# kooz_v0_1.net
KiCad netlist of a schematic drawn in EAGLE
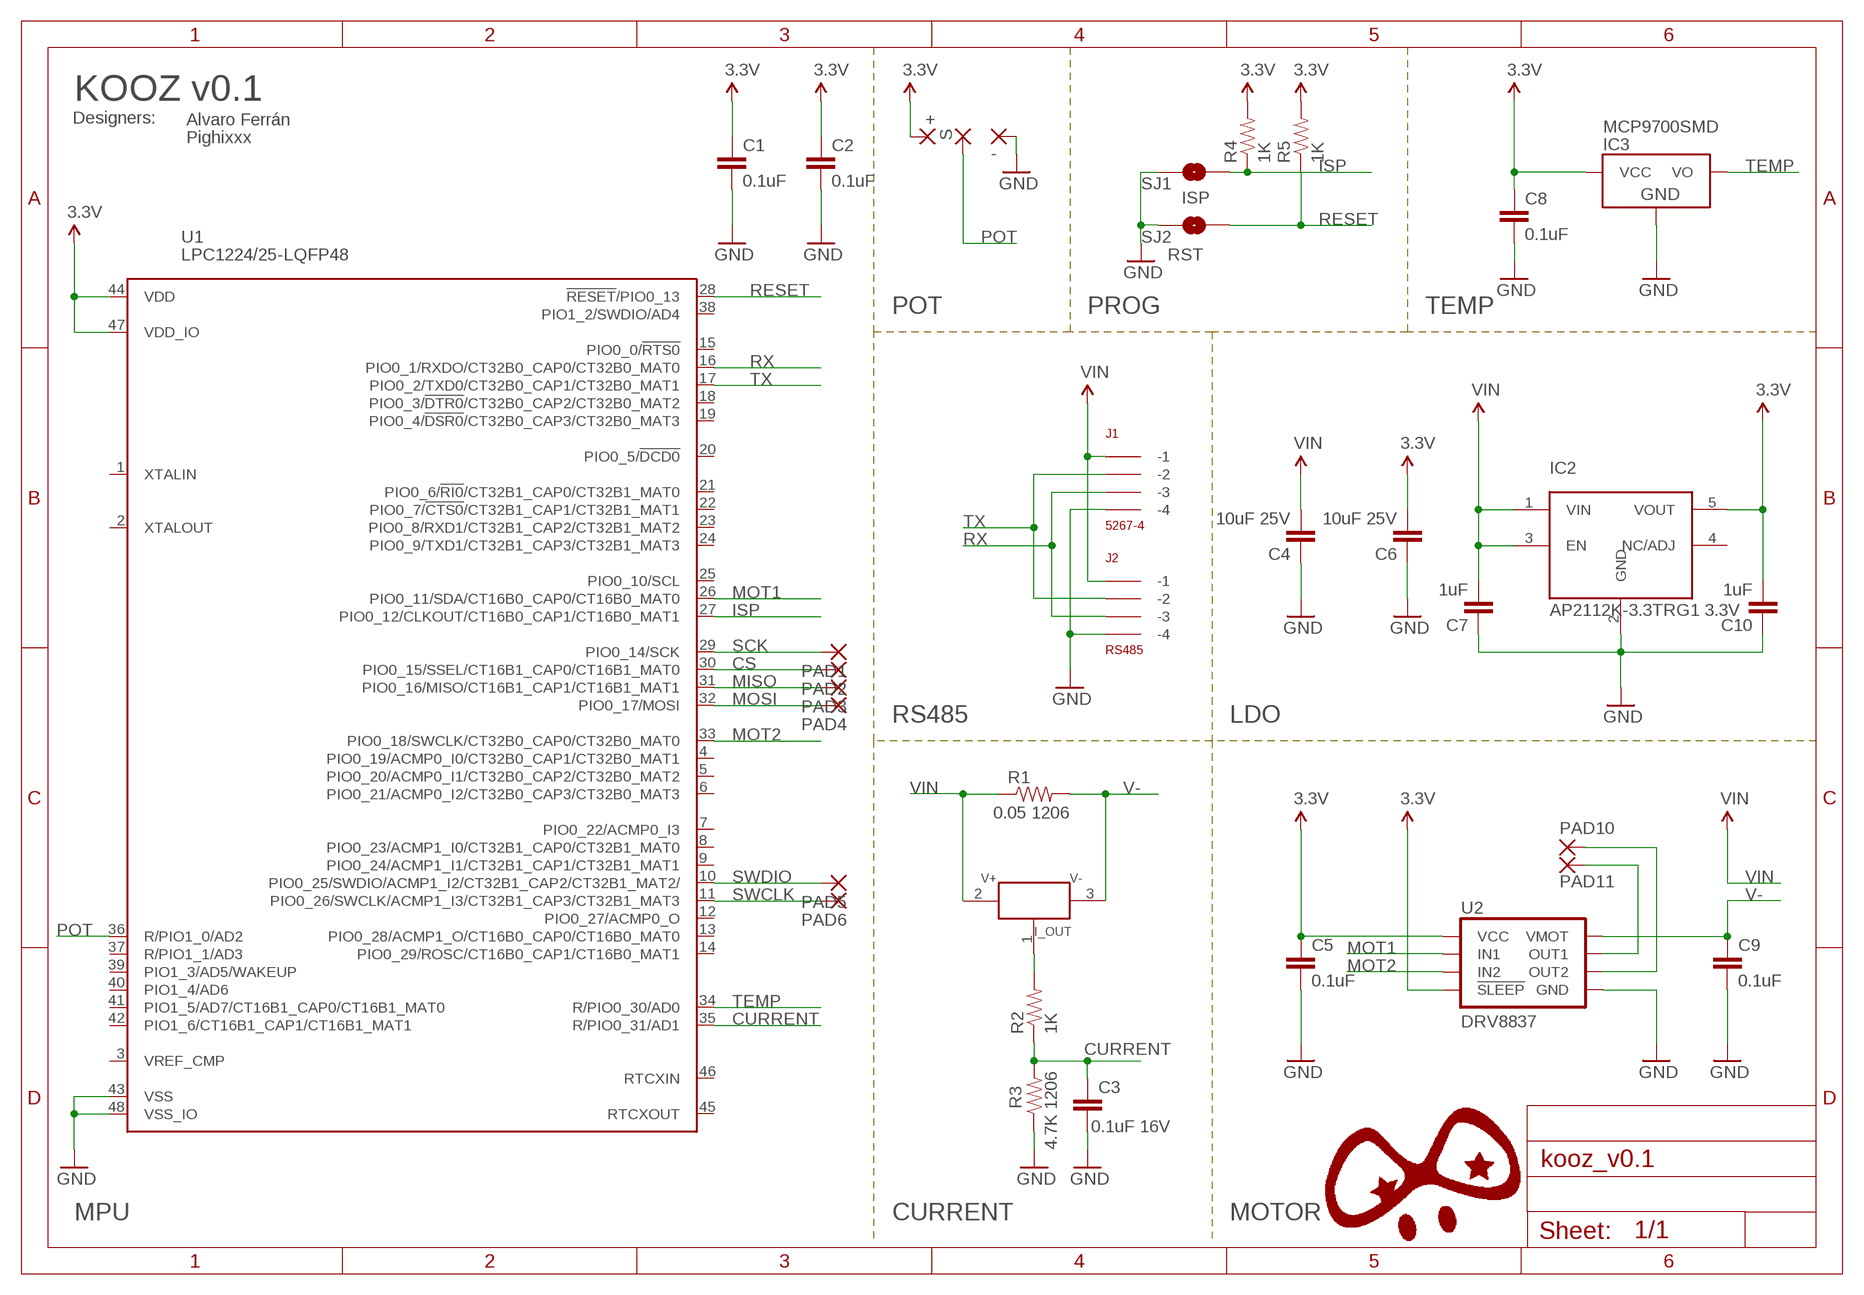
[diagram p0: schematic, sheet 1]

(export (version "E")
  (design (tool "Eeschema 10.0.6"))
  (components
    (comp (ref "C1")
      (value "0.1uF")
      (footprint "eagle-import:0402-CAP")
      (libsource (lib "eagle-import") (part "CAP0402-CAP"))
    )
    (comp (ref "C2")
      (value "0.1uF")
      (footprint "eagle-import:0402-CAP")
      (libsource (lib "eagle-import") (part "CAP0402-CAP"))
    )
    (comp (ref "C3")
      (value "0.1uF 16V")
      (footprint "eagle-import:0402-CAP")
      (libsource (lib "eagle-import") (part "CAP0402-CAP"))
    )
    (comp (ref "C4")
      (value "10uF 25V")
      (footprint "eagle-import:0603-CAP")
      (libsource (lib "eagle-import") (part "CAP0603-CAP"))
    )
    (comp (ref "C5")
      (value "0.1uF")
      (footprint "eagle-import:0402-CAP")
      (libsource (lib "eagle-import") (part "CAP0402-CAP"))
    )
    (comp (ref "C6")
      (value "10uF 25V")
      (footprint "eagle-import:0603-CAP")
      (libsource (lib "eagle-import") (part "CAP0603-CAP"))
    )
    (comp (ref "C7")
      (value "1uF")
      (footprint "eagle-import:0402-CAP")
      (libsource (lib "eagle-import") (part "CAP0402-CAP"))
    )
    (comp (ref "C8")
      (value "0.1uF")
      (footprint "eagle-import:0402-CAP")
      (libsource (lib "eagle-import") (part "CAP0402-CAP"))
    )
    (comp (ref "C9")
      (value "0.1uF")
      (footprint "eagle-import:0402-CAP")
      (libsource (lib "eagle-import") (part "CAP0402-CAP"))
    )
    (comp (ref "C10")
      (value "1uF")
      (footprint "eagle-import:0402-CAP")
      (libsource (lib "eagle-import") (part "CAP0402-CAP"))
    )
    (comp (ref "IC1")
      (value "ZXCT1008")
      (footprint "eagle-import:SOT23")
      (libsource (lib "eagle-import") (part "ZXCT1008"))
    )
    (comp (ref "IC2")
      (value "AP2112K-3.3TRG1 3.3V")
      (footprint "eagle-import:SOT23-5")
      (libsource (lib "eagle-import") (part "5PIN_REG"))
    )
    (comp (ref "IC3")
      (value "MCP9700SMD")
      (footprint "eagle-import:SOT23-3")
      (libsource (lib "eagle-import") (part "MCP9700SMD"))
    )
    (comp (ref "J1")
      (value "5267-4")
      (footprint "eagle-import:5267-4")
      (libsource (lib "eagle-import") (part "5267-4"))
    )
    (comp (ref "J2")
      (value "RS485")
      (footprint "eagle-import:5267-4")
      (libsource (lib "eagle-import") (part "5267-4"))
    )
    (comp (ref "PAD1")
      (value "SMD2")
      (footprint "eagle-import:SMD1,27-2,54")
      (libsource (lib "eagle-import") (part "SMD2"))
    )
    (comp (ref "PAD2")
      (value "SMD2")
      (footprint "eagle-import:SMD1,27-2,54")
      (libsource (lib "eagle-import") (part "SMD2"))
    )
    (comp (ref "PAD3")
      (value "SMD2")
      (footprint "eagle-import:SMD1,27-2,54")
      (libsource (lib "eagle-import") (part "SMD2"))
    )
    (comp (ref "PAD4")
      (value "SMD2")
      (footprint "eagle-import:SMD1,27-2,54")
      (libsource (lib "eagle-import") (part "SMD2"))
    )
    (comp (ref "PAD5")
      (value "SMD2")
      (footprint "eagle-import:SMD1,27-2,54")
      (libsource (lib "eagle-import") (part "SMD2"))
    )
    (comp (ref "PAD6")
      (value "SMD2")
      (footprint "eagle-import:SMD1,27-2,54")
      (libsource (lib "eagle-import") (part "SMD2"))
    )
    (comp (ref "PAD7")
      (value "+")
      (footprint "eagle-import:2,54_1,1")
      (libsource (lib "eagle-import") (part "2,54/1,1"))
    )
    (comp (ref "PAD8")
      (value "S")
      (footprint "eagle-import:2,54_1,1")
      (libsource (lib "eagle-import") (part "2,54/1,1"))
    )
    (comp (ref "PAD9")
      (value "-")
      (footprint "eagle-import:2,54_1,1")
      (libsource (lib "eagle-import") (part "2,54/1,1"))
    )
    (comp (ref "PAD10")
      (value "2,54/1,1")
      (footprint "eagle-import:2,54_1,1")
      (libsource (lib "eagle-import") (part "2,54/1,1"))
    )
    (comp (ref "PAD11")
      (value "2,54/1,1")
      (footprint "eagle-import:2,54_1,1")
      (libsource (lib "eagle-import") (part "2,54/1,1"))
    )
    (comp (ref "R1")
      (value "0.05 1206")
      (footprint "eagle-import:1206-RES")
      (libsource (lib "eagle-import") (part "RESISTOR"))
    )
    (comp (ref "R2")
      (value "1K")
      (footprint "eagle-import:0402-RES")
      (libsource (lib "eagle-import") (part "RESISTOR0402-RES"))
    )
    (comp (ref "R3")
      (value "4.7K 1206")
      (footprint "eagle-import:1206-RES")
      (libsource (lib "eagle-import") (part "RESISTOR"))
    )
    (comp (ref "R4")
      (value "1K")
      (footprint "eagle-import:0402-RES")
      (libsource (lib "eagle-import") (part "RESISTOR0402-RES"))
    )
    (comp (ref "R5")
      (value "1K")
      (footprint "eagle-import:0402-RES")
      (libsource (lib "eagle-import") (part "RESISTOR0402-RES"))
    )
    (comp (ref "SJ1")
      (value "ISP")
      (footprint "eagle-import:SJ_2S-NO")
      (libsource (lib "eagle-import") (part "SOLDERJUMPERNO"))
    )
    (comp (ref "SJ2")
      (value "RST")
      (footprint "eagle-import:SJ_2S-NO")
      (libsource (lib "eagle-import") (part "SOLDERJUMPERNO"))
    )
    (comp (ref "U1")
      (value "LPC1224/25-LQFP48")
      (footprint "eagle-import:LQFP48")
      (libsource (lib "eagle-import") (part "LPC1224/25-LQFP48"))
    )
    (comp (ref "U2")
      (value "DRV8837")
      (footprint "eagle-import:DSG")
      (libsource (lib "eagle-import") (part "DRV8837"))
    )
  )
  (nets
    (net (code "1") (name "/CS") (class "Default")
      (node (ref "PAD2") (pin "1") (pinfunction "P_1") (pintype "passive"))
      (node (ref "U1") (pin "30") (pinfunction "PIO0_15/SSEL/CT16B1_CAP0/CT16B1_MAT0_30") (pintype "bidirectional"))
    )
    (net (code "2") (name "/CURRENT") (class "Default")
      (node (ref "C3") (pin "1") (pinfunction "1_1") (pintype "passive"))
      (node (ref "R2") (pin "1") (pinfunction "1_1") (pintype "passive"))
      (node (ref "R3") (pin "2") (pinfunction "2_2") (pintype "passive"))
      (node (ref "U1") (pin "35") (pinfunction "R/PIO0_31/AD1_35") (pintype "bidirectional"))
    )
    (net (code "3") (name "/ISP") (class "Default")
      (node (ref "R4") (pin "1") (pinfunction "1_1") (pintype "passive"))
      (node (ref "SJ1") (pin "2") (pinfunction "2_2") (pintype "passive"))
      (node (ref "U1") (pin "27") (pinfunction "PIO0_12/CLKOUT/CT16B0_CAP1/CT16B0_MAT1_27") (pintype "bidirectional"))
    )
    (net (code "4") (name "/MISO") (class "Default")
      (node (ref "PAD3") (pin "1") (pinfunction "P_1") (pintype "passive"))
      (node (ref "U1") (pin "31") (pinfunction "PIO0_16/MISO/CT16B1_CAP1/CT16B1_MAT1_31") (pintype "bidirectional"))
    )
    (net (code "5") (name "/MOSI") (class "Default")
      (node (ref "PAD4") (pin "1") (pinfunction "P_1") (pintype "passive"))
      (node (ref "U1") (pin "32") (pinfunction "PIO0_17/MOSI_32") (pintype "bidirectional"))
    )
    (net (code "6") (name "/MOT1") (class "Default")
      (node (ref "U1") (pin "26") (pinfunction "PIO0_11/SDA/CT16B0_CAP0/CT16B0_MAT0_26") (pintype "bidirectional"))
      (node (ref "U2") (pin "6") (pinfunction "IN1_6") (pintype "bidirectional"))
    )
    (net (code "7") (name "/MOT2") (class "Default")
      (node (ref "U1") (pin "33") (pinfunction "PIO0_18/SWCLK/CT32B0_CAP0/CT32B0_MAT0_33") (pintype "bidirectional"))
      (node (ref "U2") (pin "5") (pinfunction "IN2_5") (pintype "bidirectional"))
    )
    (net (code "8") (name "/POT") (class "Default")
      (node (ref "PAD8") (pin "1") (pinfunction "P_1") (pintype "passive"))
      (node (ref "U1") (pin "36") (pinfunction "R/PIO1_0/AD2_36") (pintype "bidirectional"))
    )
    (net (code "9") (name "/RESET") (class "Default")
      (node (ref "R5") (pin "1") (pinfunction "1_1") (pintype "passive"))
      (node (ref "SJ2") (pin "2") (pinfunction "2_2") (pintype "passive"))
      (node (ref "U1") (pin "28") (pinfunction "~{RESET}/PIO0_13_28") (pintype "bidirectional"))
    )
    (net (code "10") (name "/RX") (class "Default")
      (node (ref "J1") (pin "P$3") (pinfunction "-3_P$3") (pintype "bidirectional"))
      (node (ref "J2") (pin "P$3") (pinfunction "-3_P$3") (pintype "bidirectional"))
      (node (ref "U1") (pin "16") (pinfunction "PIO0_1/RXDO/CT32B0_CAP0/CT32B0_MAT0_16") (pintype "bidirectional"))
    )
    (net (code "11") (name "/SCK") (class "Default")
      (node (ref "PAD1") (pin "1") (pinfunction "P_1") (pintype "passive"))
      (node (ref "U1") (pin "29") (pinfunction "PIO0_14/SCK_29") (pintype "bidirectional"))
    )
    (net (code "12") (name "/SWCLK") (class "Default")
      (node (ref "PAD6") (pin "1") (pinfunction "P_1") (pintype "passive"))
      (node (ref "U1") (pin "11") (pinfunction "PIO0_26/SWCLK/ACMP1_I3/CT32B1_CAP3/CT32B1_MAT3_11") (pintype "bidirectional"))
    )
    (net (code "13") (name "/SWDIO") (class "Default")
      (node (ref "PAD5") (pin "1") (pinfunction "P_1") (pintype "passive"))
      (node (ref "U1") (pin "10") (pinfunction "PIO0_25/SWDIO/ACMP1_I2/CT32B1_CAP2/CT32B1_MAT2/_10") (pintype "bidirectional"))
    )
    (net (code "14") (name "/TEMP") (class "Default")
      (node (ref "IC3") (pin "2") (pinfunction "VO_2") (pintype "bidirectional"))
      (node (ref "U1") (pin "34") (pinfunction "R/PIO0_30/AD0_34") (pintype "bidirectional"))
    )
    (net (code "15") (name "/TX") (class "Default")
      (node (ref "J1") (pin "P$2") (pinfunction "-2_P$2") (pintype "bidirectional"))
      (node (ref "J2") (pin "P$2") (pinfunction "-2_P$2") (pintype "bidirectional"))
      (node (ref "U1") (pin "17") (pinfunction "PIO0_2/TXD0/CT32B0_CAP1/CT32B0_MAT1_17") (pintype "bidirectional"))
    )
    (net (code "16") (name "/V-") (class "Default")
      (node (ref "C9") (pin "1") (pinfunction "1_1") (pintype "passive"))
      (node (ref "IC1") (pin "3") (pinfunction "V-_3") (pintype "bidirectional"))
      (node (ref "R1") (pin "2") (pinfunction "2_2") (pintype "passive"))
      (node (ref "U2") (pin "1") (pinfunction "VMOT_1") (pintype "bidirectional"))
    )
    (net (code "17") (name "3.3V") (class "Default")
      (node (ref "C1") (pin "1") (pinfunction "1_1") (pintype "passive"))
      (node (ref "C10") (pin "2") (pinfunction "2_2") (pintype "passive"))
      (node (ref "C2") (pin "1") (pinfunction "1_1") (pintype "passive"))
      (node (ref "C5") (pin "1") (pinfunction "1_1") (pintype "passive"))
      (node (ref "C6") (pin "2") (pinfunction "2_2") (pintype "passive"))
      (node (ref "C8") (pin "1") (pinfunction "1_1") (pintype "passive"))
      (node (ref "IC2") (pin "5") (pinfunction "VOUT_5") (pintype "bidirectional"))
      (node (ref "IC3") (pin "1") (pinfunction "VCC_1") (pintype "bidirectional"))
      (node (ref "PAD7") (pin "1") (pinfunction "P_1") (pintype "passive"))
      (node (ref "R4") (pin "2") (pinfunction "2_2") (pintype "passive"))
      (node (ref "R5") (pin "2") (pinfunction "2_2") (pintype "passive"))
      (node (ref "U1") (pin "44") (pinfunction "VDD_44") (pintype "power_in"))
      (node (ref "U1") (pin "47") (pinfunction "VDD_IO_47") (pintype "power_in"))
      (node (ref "U2") (pin "7") (pinfunction "~{SLEEP}_7") (pintype "bidirectional"))
      (node (ref "U2") (pin "8") (pinfunction "VCC_8") (pintype "bidirectional"))
    )
    (net (code "18") (name "GND") (class "Default")
      (node (ref "C1") (pin "2") (pinfunction "2_2") (pintype "passive"))
      (node (ref "C10") (pin "1") (pinfunction "1_1") (pintype "passive"))
      (node (ref "C2") (pin "2") (pinfunction "2_2") (pintype "passive"))
      (node (ref "C3") (pin "2") (pinfunction "2_2") (pintype "passive"))
      (node (ref "C4") (pin "1") (pinfunction "1_1") (pintype "passive"))
      (node (ref "C5") (pin "2") (pinfunction "2_2") (pintype "passive"))
      (node (ref "C6") (pin "1") (pinfunction "1_1") (pintype "passive"))
      (node (ref "C7") (pin "1") (pinfunction "1_1") (pintype "passive"))
      (node (ref "C8") (pin "2") (pinfunction "2_2") (pintype "passive"))
      (node (ref "C9") (pin "2") (pinfunction "2_2") (pintype "passive"))
      (node (ref "IC2") (pin "2") (pinfunction "GND_2") (pintype "bidirectional"))
      (node (ref "IC3") (pin "3") (pinfunction "GND_3") (pintype "bidirectional"))
      (node (ref "J1") (pin "P$4") (pinfunction "-4_P$4") (pintype "bidirectional"))
      (node (ref "J2") (pin "P$4") (pinfunction "-4_P$4") (pintype "bidirectional"))
      (node (ref "PAD9") (pin "1") (pinfunction "P_1") (pintype "passive"))
      (node (ref "R3") (pin "1") (pinfunction "1_1") (pintype "passive"))
      (node (ref "SJ1") (pin "1") (pinfunction "1_1") (pintype "passive"))
      (node (ref "SJ2") (pin "1") (pinfunction "1_1") (pintype "passive"))
      (node (ref "U1") (pin "43") (pinfunction "VSS_43") (pintype "power_in"))
      (node (ref "U1") (pin "48") (pinfunction "VSS_IO_48") (pintype "power_in"))
      (node (ref "U2") (pin "4") (pinfunction "GND_4") (pintype "bidirectional"))
      (node (ref "U2") (pin "PAD") (pinfunction "GND_PAD") (pintype "bidirectional"))
    )
    (net (code "19") (name "Net-(IC1-I_OUT)") (class "Default")
      (node (ref "IC1") (pin "1") (pinfunction "I_OUT_1") (pintype "bidirectional"))
      (node (ref "R2") (pin "2") (pinfunction "2_2") (pintype "passive"))
    )
    (net (code "20") (name "Net-(PAD10-P)") (class "Default")
      (node (ref "PAD10") (pin "1") (pinfunction "P_1") (pintype "passive"))
      (node (ref "U2") (pin "3") (pinfunction "OUT2_3") (pintype "bidirectional"))
    )
    (net (code "21") (name "Net-(PAD11-P)") (class "Default")
      (node (ref "PAD11") (pin "1") (pinfunction "P_1") (pintype "passive"))
      (node (ref "U2") (pin "2") (pinfunction "OUT1_2") (pintype "bidirectional"))
    )
    (net (code "22") (name "VIN") (class "Default")
      (node (ref "C4") (pin "2") (pinfunction "2_2") (pintype "passive"))
      (node (ref "C7") (pin "2") (pinfunction "2_2") (pintype "passive"))
      (node (ref "IC1") (pin "2") (pinfunction "V+_2") (pintype "bidirectional"))
      (node (ref "IC2") (pin "1") (pinfunction "VIN_1") (pintype "bidirectional"))
      (node (ref "IC2") (pin "3") (pinfunction "EN_3") (pintype "bidirectional"))
      (node (ref "J1") (pin "P$1") (pinfunction "-1_P$1") (pintype "bidirectional"))
      (node (ref "J2") (pin "P$1") (pinfunction "-1_P$1") (pintype "bidirectional"))
      (node (ref "R1") (pin "1") (pinfunction "1_1") (pintype "passive"))
    )
    (net (code "23") (name "unconnected-(IC2-NC{slash}ADJ-Pad4)") (class "Default")
      (node (ref "IC2") (pin "4") (pinfunction "NC/ADJ_4") (pintype "bidirectional"))
    )
    (net (code "24") (name "unconnected-(U1-PIO0_0{slash}~{RTS0}-Pad15)") (class "Default")
      (node (ref "U1") (pin "15") (pinfunction "PIO0_0/~{RTS0}_15") (pintype "bidirectional"))
    )
    (net (code "25") (name "unconnected-(U1-PIO0_3{slash}~{DTR0}{slash}CT32B0_CAP2{slash}CT32B0_MAT2-Pad18)") (class "Default")
      (node (ref "U1") (pin "18") (pinfunction "PIO0_3/~{DTR0}/CT32B0_CAP2/CT32B0_MAT2_18") (pintype "bidirectional"))
    )
    (net (code "26") (name "unconnected-(U1-PIO0_4{slash}~{DSR0}{slash}CT32B0_CAP3{slash}CT32B0_MAT3-Pad19)") (class "Default")
      (node (ref "U1") (pin "19") (pinfunction "PIO0_4/~{DSR0}/CT32B0_CAP3/CT32B0_MAT3_19") (pintype "bidirectional"))
    )
    (net (code "27") (name "unconnected-(U1-PIO0_5{slash}~{DCD0}-Pad20)") (class "Default")
      (node (ref "U1") (pin "20") (pinfunction "PIO0_5/~{DCD0}_20") (pintype "bidirectional"))
    )
    (net (code "28") (name "unconnected-(U1-PIO0_6{slash}~{RI0}{slash}CT32B1_CAP0{slash}CT32B1_MAT0-Pad21)") (class "Default")
      (node (ref "U1") (pin "21") (pinfunction "PIO0_6/~{RI0}/CT32B1_CAP0/CT32B1_MAT0_21") (pintype "bidirectional"))
    )
    (net (code "29") (name "unconnected-(U1-PIO0_7{slash}~{CTS0}{slash}CT32B1_CAP1{slash}CT32B1_MAT1-Pad22)") (class "Default")
      (node (ref "U1") (pin "22") (pinfunction "PIO0_7/~{CTS0}/CT32B1_CAP1/CT32B1_MAT1_22") (pintype "bidirectional"))
    )
    (net (code "30") (name "unconnected-(U1-PIO0_8{slash}RXD1{slash}CT32B1_CAP2{slash}CT32B1_MAT2-Pad23)") (class "Default")
      (node (ref "U1") (pin "23") (pinfunction "PIO0_8/RXD1/CT32B1_CAP2/CT32B1_MAT2_23") (pintype "bidirectional"))
    )
    (net (code "31") (name "unconnected-(U1-PIO0_9{slash}TXD1{slash}CT32B1_CAP3{slash}CT32B1_MAT3-Pad24)") (class "Default")
      (node (ref "U1") (pin "24") (pinfunction "PIO0_9/TXD1/CT32B1_CAP3/CT32B1_MAT3_24") (pintype "bidirectional"))
    )
    (net (code "32") (name "unconnected-(U1-PIO0_10{slash}SCL-Pad25)") (class "Default")
      (node (ref "U1") (pin "25") (pinfunction "PIO0_10/SCL_25") (pintype "bidirectional"))
    )
    (net (code "33") (name "unconnected-(U1-PIO0_19{slash}ACMP0_I0{slash}CT32B0_CAP1{slash}CT32B0_MAT1-Pad4)") (class "Default")
      (node (ref "U1") (pin "4") (pinfunction "PIO0_19/ACMP0_I0/CT32B0_CAP1/CT32B0_MAT1_4") (pintype "bidirectional"))
    )
    (net (code "34") (name "unconnected-(U1-PIO0_20{slash}ACMP0_I1{slash}CT32B0_CAP2{slash}CT32B0_MAT2-Pad5)") (class "Default")
      (node (ref "U1") (pin "5") (pinfunction "PIO0_20/ACMP0_I1/CT32B0_CAP2/CT32B0_MAT2_5") (pintype "bidirectional"))
    )
    (net (code "35") (name "unconnected-(U1-PIO0_21{slash}ACMP0_I2{slash}CT32B0_CAP3{slash}CT32B0_MAT3-Pad6)") (class "Default")
      (node (ref "U1") (pin "6") (pinfunction "PIO0_21/ACMP0_I2/CT32B0_CAP3/CT32B0_MAT3_6") (pintype "bidirectional"))
    )
    (net (code "36") (name "unconnected-(U1-PIO0_22{slash}ACMP0_I3-Pad7)") (class "Default")
      (node (ref "U1") (pin "7") (pinfunction "PIO0_22/ACMP0_I3_7") (pintype "bidirectional"))
    )
    (net (code "37") (name "unconnected-(U1-PIO0_23{slash}ACMP1_I0{slash}CT32B1_CAP0{slash}CT32B1_MAT0-Pad8)") (class "Default")
      (node (ref "U1") (pin "8") (pinfunction "PIO0_23/ACMP1_I0/CT32B1_CAP0/CT32B1_MAT0_8") (pintype "bidirectional"))
    )
    (net (code "38") (name "unconnected-(U1-PIO0_24{slash}ACMP1_I1{slash}CT32B1_CAP1{slash}CT32B1_MAT1-Pad9)") (class "Default")
      (node (ref "U1") (pin "9") (pinfunction "PIO0_24/ACMP1_I1/CT32B1_CAP1/CT32B1_MAT1_9") (pintype "bidirectional"))
    )
    (net (code "39") (name "unconnected-(U1-PIO0_27{slash}ACMP0_O-Pad12)") (class "Default")
      (node (ref "U1") (pin "12") (pinfunction "PIO0_27/ACMP0_O_12") (pintype "bidirectional"))
    )
    (net (code "40") (name "unconnected-(U1-PIO0_28{slash}ACMP1_O{slash}CT16B0_CAP0{slash}CT16B0_MAT0-Pad13)") (class "Default")
      (node (ref "U1") (pin "13") (pinfunction "PIO0_28/ACMP1_O/CT16B0_CAP0/CT16B0_MAT0_13") (pintype "bidirectional"))
    )
    (net (code "41") (name "unconnected-(U1-PIO0_29{slash}ROSC{slash}CT16B0_CAP1{slash}CT16B0_MAT1-Pad14)") (class "Default")
      (node (ref "U1") (pin "14") (pinfunction "PIO0_29/ROSC/CT16B0_CAP1/CT16B0_MAT1_14") (pintype "bidirectional"))
    )
    (net (code "42") (name "unconnected-(U1-PIO1_2{slash}SWDIO{slash}AD4-Pad38)") (class "Default")
      (node (ref "U1") (pin "38") (pinfunction "PIO1_2/SWDIO/AD4_38") (pintype "bidirectional"))
    )
    (net (code "43") (name "unconnected-(U1-PIO1_3{slash}AD5{slash}WAKEUP-Pad39)") (class "Default")
      (node (ref "U1") (pin "39") (pinfunction "PIO1_3/AD5/WAKEUP_39") (pintype "bidirectional"))
    )
    (net (code "44") (name "unconnected-(U1-PIO1_4{slash}AD6-Pad40)") (class "Default")
      (node (ref "U1") (pin "40") (pinfunction "PIO1_4/AD6_40") (pintype "bidirectional"))
    )
    (net (code "45") (name "unconnected-(U1-PIO1_5{slash}AD7{slash}CT16B1_CAP0{slash}CT16B1_MAT0-Pad41)") (class "Default")
      (node (ref "U1") (pin "41") (pinfunction "PIO1_5/AD7/CT16B1_CAP0/CT16B1_MAT0_41") (pintype "bidirectional"))
    )
    (net (code "46") (name "unconnected-(U1-PIO1_6{slash}CT16B1_CAP1{slash}CT16B1_MAT1-Pad42)") (class "Default")
      (node (ref "U1") (pin "42") (pinfunction "PIO1_6/CT16B1_CAP1/CT16B1_MAT1_42") (pintype "bidirectional"))
    )
    (net (code "47") (name "unconnected-(U1-RTCXIN-Pad46)") (class "Default")
      (node (ref "U1") (pin "46") (pinfunction "RTCXIN_46") (pintype "bidirectional"))
    )
    (net (code "48") (name "unconnected-(U1-RTCXOUT-Pad45)") (class "Default")
      (node (ref "U1") (pin "45") (pinfunction "RTCXOUT_45") (pintype "bidirectional"))
    )
    (net (code "49") (name "unconnected-(U1-R{slash}PIO1_1{slash}AD3-Pad37)") (class "Default")
      (node (ref "U1") (pin "37") (pinfunction "R/PIO1_1/AD3_37") (pintype "bidirectional"))
    )
    (net (code "50") (name "unconnected-(U1-VREF_CMP-Pad3)") (class "Default")
      (node (ref "U1") (pin "3") (pinfunction "VREF_CMP_3") (pintype "bidirectional"))
    )
    (net (code "51") (name "unconnected-(U1-XTALIN-Pad1)") (class "Default")
      (node (ref "U1") (pin "1") (pinfunction "XTALIN_1") (pintype "passive"))
    )
    (net (code "52") (name "unconnected-(U1-XTALOUT-Pad2)") (class "Default")
      (node (ref "U1") (pin "2") (pinfunction "XTALOUT_2") (pintype "passive"))
    )
  )
)
